# matherBoard.net
KiCad netlist of a schematic drawn in EAGLE
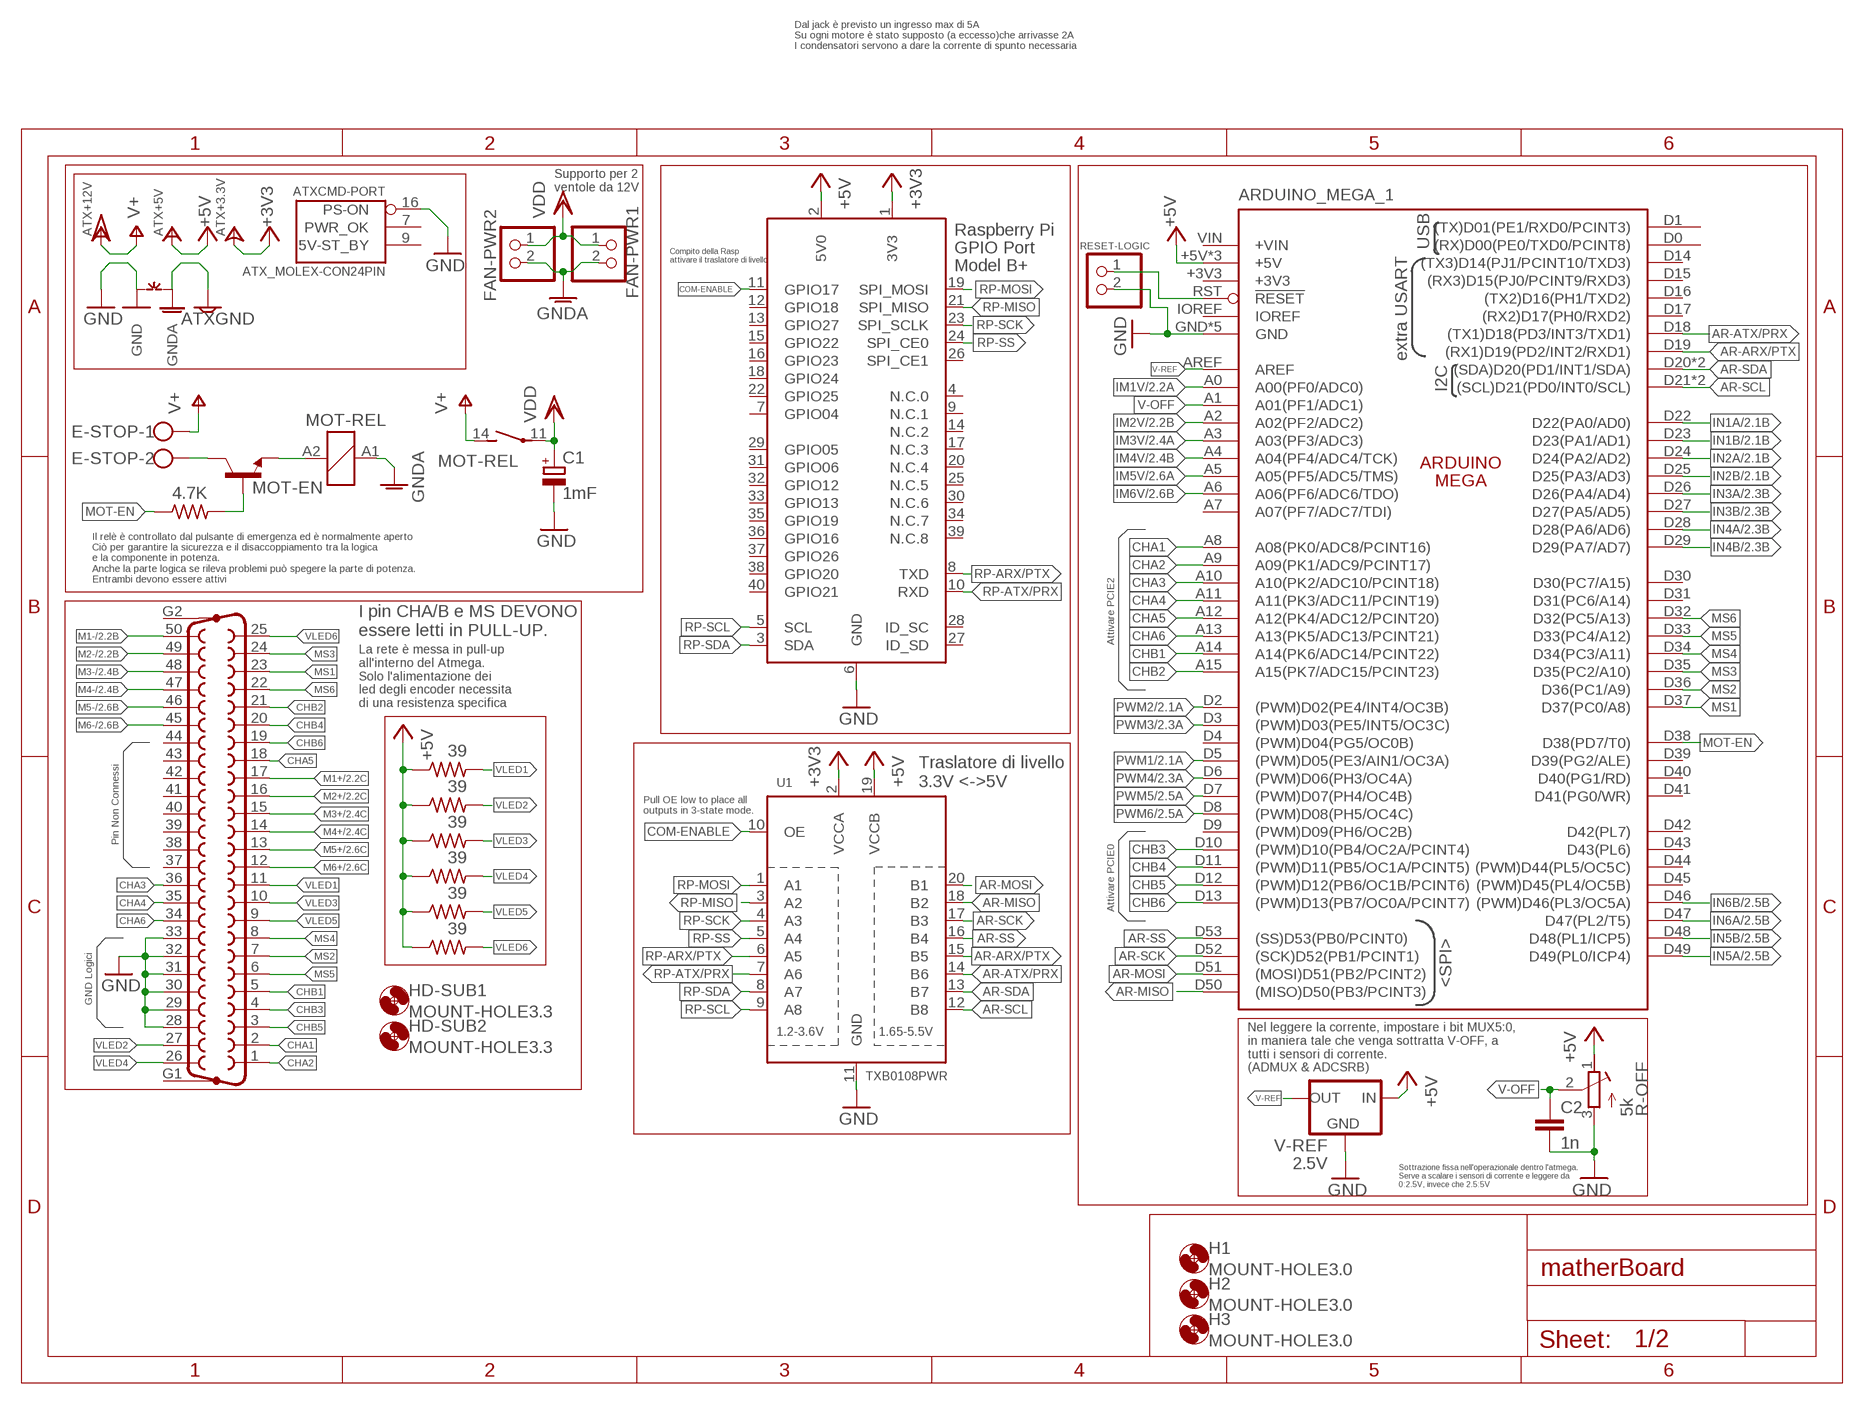
[diagram p0: schematic, sheet 1]
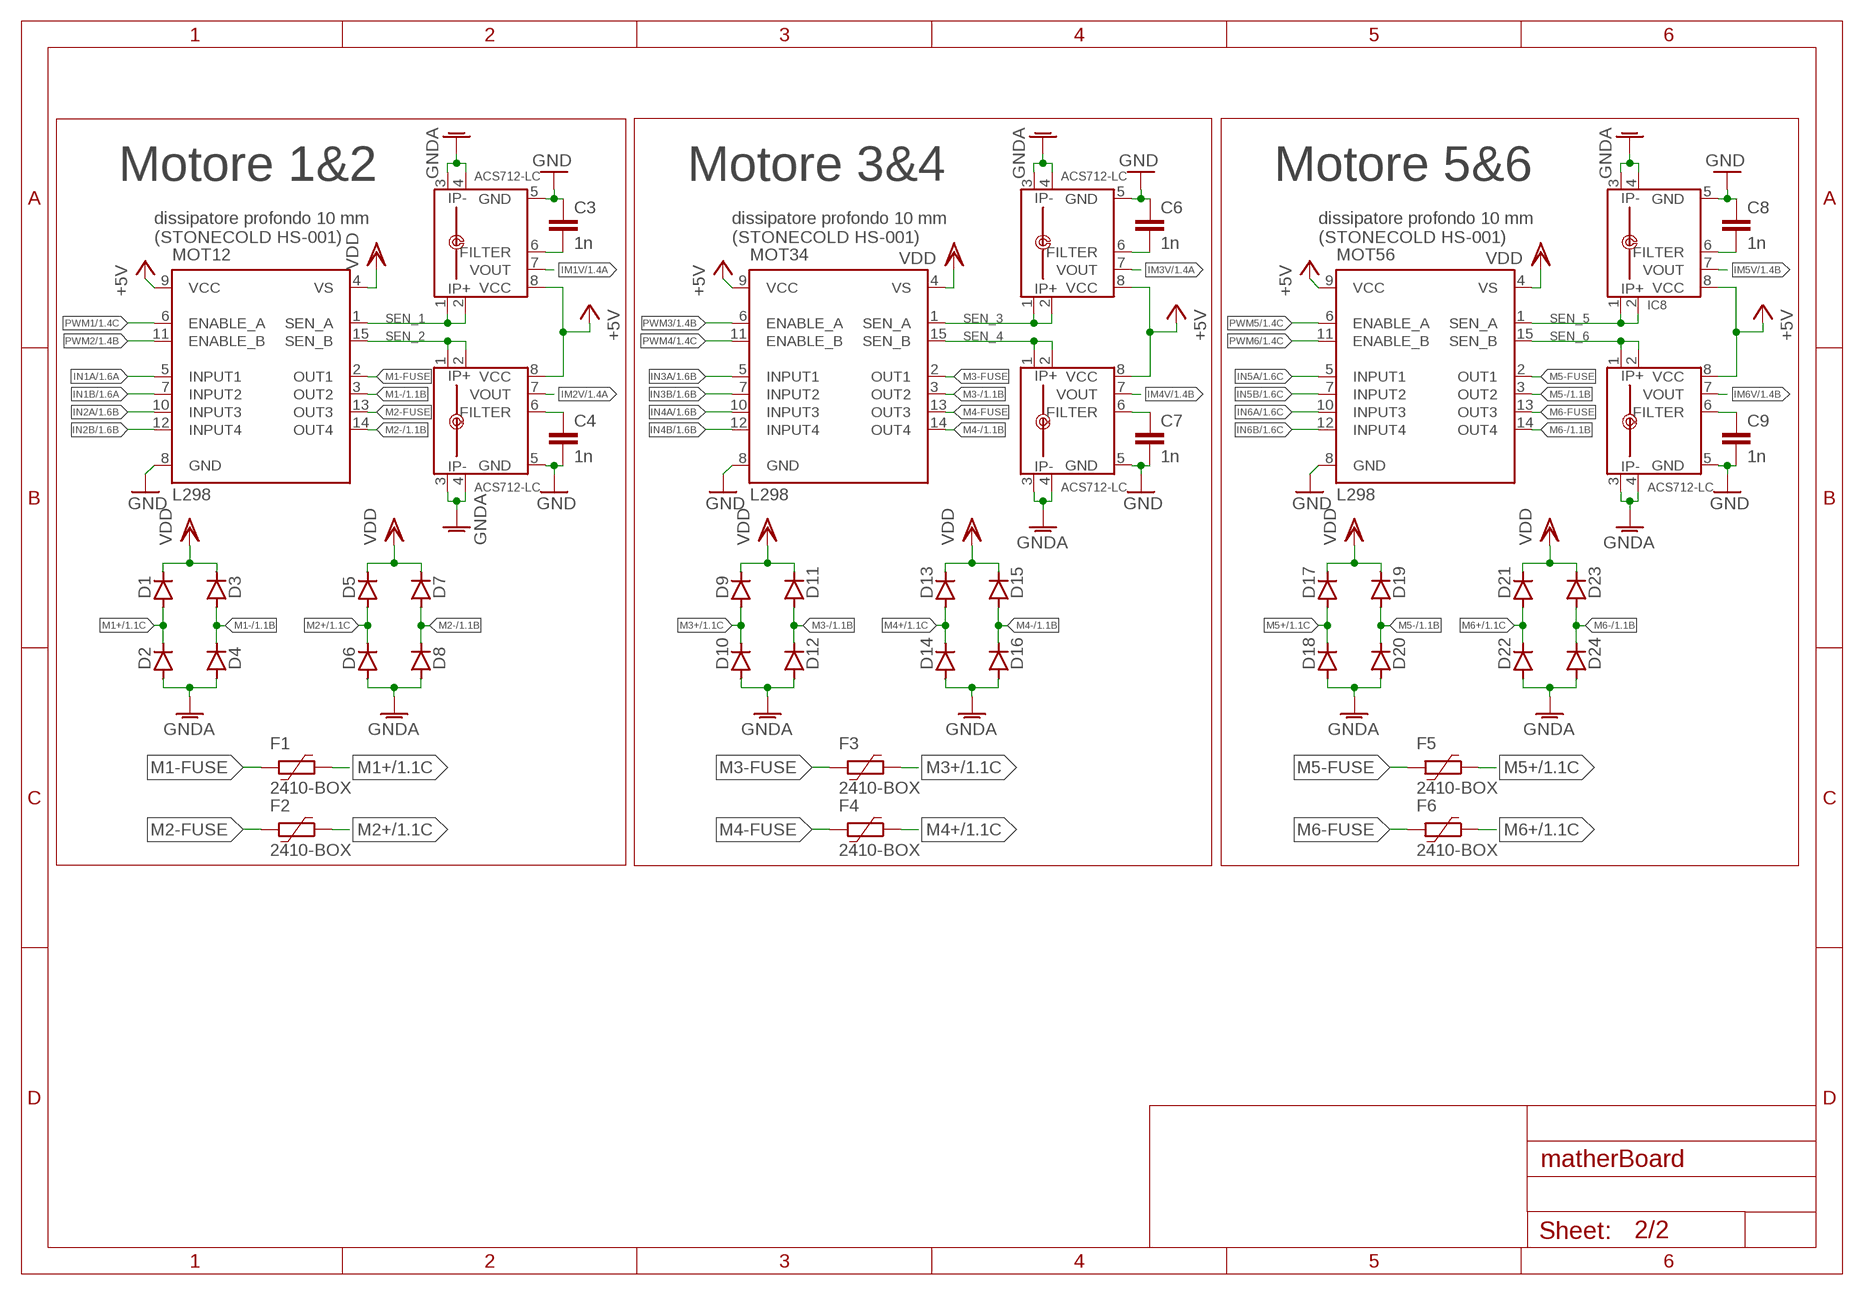
[diagram p1: schematic, sheet 2]

(export (version "E")
  (design (tool "Eeschema 10.0.6"))
  (components
    (comp (ref "C3")
      (value "1n")
      (footprint "eagle-import:C025-024X044")
      (libsource (lib "eagle-import") (part "C-EU025-024X044"))
    )
    (comp (ref "C4")
      (value "1n")
      (footprint "eagle-import:C025-024X044")
      (libsource (lib "eagle-import") (part "C-EU025-024X044"))
    )
    (comp (ref "C6")
      (value "1n")
      (footprint "eagle-import:C025-024X044")
      (libsource (lib "eagle-import") (part "C-EU025-024X044"))
    )
    (comp (ref "C7")
      (value "1n")
      (footprint "eagle-import:C025-024X044")
      (libsource (lib "eagle-import") (part "C-EU025-024X044"))
    )
    (comp (ref "C8")
      (value "1n")
      (footprint "eagle-import:C025-024X044")
      (libsource (lib "eagle-import") (part "C-EU025-024X044"))
    )
    (comp (ref "C9")
      (value "1n")
      (footprint "eagle-import:C025-024X044")
      (libsource (lib "eagle-import") (part "C-EU025-024X044"))
    )
    (comp (ref "D1")
      (value "ES2D")
      (footprint "eagle-import:SMB")
      (libsource (lib "eagle-import") (part "ES2D"))
    )
    (comp (ref "D2")
      (value "ES2D")
      (footprint "eagle-import:SMB")
      (libsource (lib "eagle-import") (part "ES2D"))
    )
    (comp (ref "D3")
      (value "ES2D")
      (footprint "eagle-import:SMB")
      (libsource (lib "eagle-import") (part "ES2D"))
    )
    (comp (ref "D4")
      (value "ES2D")
      (footprint "eagle-import:SMB")
      (libsource (lib "eagle-import") (part "ES2D"))
    )
    (comp (ref "D5")
      (value "ES2D")
      (footprint "eagle-import:SMB")
      (libsource (lib "eagle-import") (part "ES2D"))
    )
    (comp (ref "D6")
      (value "ES2D")
      (footprint "eagle-import:SMB")
      (libsource (lib "eagle-import") (part "ES2D"))
    )
    (comp (ref "D7")
      (value "ES2D")
      (footprint "eagle-import:SMB")
      (libsource (lib "eagle-import") (part "ES2D"))
    )
    (comp (ref "D8")
      (value "ES2D")
      (footprint "eagle-import:SMB")
      (libsource (lib "eagle-import") (part "ES2D"))
    )
    (comp (ref "D9")
      (value "ES2D")
      (footprint "eagle-import:SMB")
      (libsource (lib "eagle-import") (part "ES2D"))
    )
    (comp (ref "D10")
      (value "ES2D")
      (footprint "eagle-import:SMB")
      (libsource (lib "eagle-import") (part "ES2D"))
    )
    (comp (ref "D11")
      (value "ES2D")
      (footprint "eagle-import:SMB")
      (libsource (lib "eagle-import") (part "ES2D"))
    )
    (comp (ref "D12")
      (value "ES2D")
      (footprint "eagle-import:SMB")
      (libsource (lib "eagle-import") (part "ES2D"))
    )
    (comp (ref "D13")
      (value "ES2D")
      (footprint "eagle-import:SMB")
      (libsource (lib "eagle-import") (part "ES2D"))
    )
    (comp (ref "D14")
      (value "ES2D")
      (footprint "eagle-import:SMB")
      (libsource (lib "eagle-import") (part "ES2D"))
    )
    (comp (ref "D15")
      (value "ES2D")
      (footprint "eagle-import:SMB")
      (libsource (lib "eagle-import") (part "ES2D"))
    )
    (comp (ref "D16")
      (value "ES2D")
      (footprint "eagle-import:SMB")
      (libsource (lib "eagle-import") (part "ES2D"))
    )
    (comp (ref "D17")
      (value "ES2D")
      (footprint "eagle-import:SMB")
      (libsource (lib "eagle-import") (part "ES2D"))
    )
    (comp (ref "D18")
      (value "ES2D")
      (footprint "eagle-import:SMB")
      (libsource (lib "eagle-import") (part "ES2D"))
    )
    (comp (ref "D19")
      (value "ES2D")
      (footprint "eagle-import:SMB")
      (libsource (lib "eagle-import") (part "ES2D"))
    )
    (comp (ref "D20")
      (value "ES2D")
      (footprint "eagle-import:SMB")
      (libsource (lib "eagle-import") (part "ES2D"))
    )
    (comp (ref "D21")
      (value "ES2D")
      (footprint "eagle-import:SMB")
      (libsource (lib "eagle-import") (part "ES2D"))
    )
    (comp (ref "D22")
      (value "ES2D")
      (footprint "eagle-import:SMB")
      (libsource (lib "eagle-import") (part "ES2D"))
    )
    (comp (ref "D23")
      (value "ES2D")
      (footprint "eagle-import:SMB")
      (libsource (lib "eagle-import") (part "ES2D"))
    )
    (comp (ref "D24")
      (value "ES2D")
      (footprint "eagle-import:SMB")
      (libsource (lib "eagle-import") (part "ES2D"))
    )
    (comp (ref "F1")
      (value "2410-BOX")
      (footprint "eagle-import:BELFUSE0679-3000-12")
      (libsource (lib "eagle-import") (part "?2410-BOX"))
    )
    (comp (ref "F2")
      (value "2410-BOX")
      (footprint "eagle-import:BELFUSE0679-3000-12")
      (libsource (lib "eagle-import") (part "?2410-BOX"))
    )
    (comp (ref "F3")
      (value "2410-BOX")
      (footprint "eagle-import:BELFUSE0679-3000-12")
      (libsource (lib "eagle-import") (part "?2410-BOX"))
    )
    (comp (ref "F4")
      (value "2410-BOX")
      (footprint "eagle-import:BELFUSE0679-3000-12")
      (libsource (lib "eagle-import") (part "?2410-BOX"))
    )
    (comp (ref "F5")
      (value "2410-BOX")
      (footprint "eagle-import:BELFUSE0679-3000-12")
      (libsource (lib "eagle-import") (part "?2410-BOX"))
    )
    (comp (ref "F6")
      (value "2410-BOX")
      (footprint "eagle-import:BELFUSE0679-3000-12")
      (libsource (lib "eagle-import") (part "?2410-BOX"))
    )
    (comp (ref "IC2")
      (value "ACS712-LC")
      (footprint "eagle-import:SOIC8")
      (libsource (lib "eagle-import") (part "ACS712-LC"))
    )
    (comp (ref "IC3")
      (value "ACS712-LC")
      (footprint "eagle-import:SOIC8")
      (libsource (lib "eagle-import") (part "ACS712-LC"))
    )
    (comp (ref "IC5")
      (value "ACS712-LC")
      (footprint "eagle-import:SOIC8")
      (libsource (lib "eagle-import") (part "ACS712-LC"))
    )
    (comp (ref "IC6")
      (value "ACS712-LC")
      (footprint "eagle-import:SOIC8")
      (libsource (lib "eagle-import") (part "ACS712-LC"))
    )
    (comp (ref "IC8")
      (value "ACS712-LC")
      (footprint "eagle-import:SOIC8")
      (libsource (lib "eagle-import") (part "ACS712-LC"))
    )
    (comp (ref "IC9")
      (value "ACS712-LC")
      (footprint "eagle-import:SOIC8")
      (libsource (lib "eagle-import") (part "ACS712-LC"))
    )
    (comp (ref "MOT12")
      (value "L298")
      (footprint "eagle-import:MULTIWATT-15")
      (fields (field (name "MPN") "L298N"))
      (libsource (lib "eagle-import") (part "L298"))
    )
    (comp (ref "MOT34")
      (value "L298")
      (footprint "eagle-import:MULTIWATT-15")
      (fields (field (name "MPN") "L298N"))
      (libsource (lib "eagle-import") (part "L298"))
    )
    (comp (ref "MOT56")
      (value "L298")
      (footprint "eagle-import:MULTIWATT-15")
      (fields (field (name "MPN") "L298N"))
      (libsource (lib "eagle-import") (part "L298"))
    )
    (comp (ref "ARDUINO_MEGA_1")
      (value "MEGA_ARDUINONO-HOLE")
      (footprint "eagle-import:MEGA-NO-HOLE")
      (libsource (lib "eagle-import") (part "MEGA_ARDUINONO-HOLE"))
    )
    (comp (ref "ATX")
      (value "ATX_MOLEX-CON24PIN")
      (footprint "eagle-import:5566-24")
      (libsource (lib "eagle-import") (part "ATX_MOLEX-CON24PIN"))
    )
    (comp (ref "C1")
      (value "1mF")
      (footprint "eagle-import:E5-13")
      (libsource (lib "eagle-import") (part "CPOL-EUE5-13"))
    )
    (comp (ref "C2")
      (value "1n")
      (footprint "eagle-import:C025-024X044")
      (libsource (lib "eagle-import") (part "C-EU025-024X044"))
    )
    (comp (ref "D-SUB50")
      (value "F50VP")
      (footprint "eagle-import:F50VP")
      (libsource (lib "eagle-import") (part "F50VP"))
    )
    (comp (ref "E-STOP")
      (value "W237-102")
      (footprint "eagle-import:W237-102")
      (fields (field (name "MPN") "237-102"))
      (libsource (lib "eagle-import") (part "W237-102"))
    )
    (comp (ref "FAN-PWR1")
      (value "PINHD-1X2")
      (footprint "eagle-import:1X02")
      (libsource (lib "eagle-import") (part "PINHD-1X2"))
    )
    (comp (ref "FAN-PWR2")
      (value "PINHD-1X2")
      (footprint "eagle-import:1X02")
      (libsource (lib "eagle-import") (part "PINHD-1X2"))
    )
    (comp (ref "H1")
      (value "MOUNT-HOLE3.0")
      (footprint "eagle-import:3,0")
      (libsource (lib "eagle-import") (part "MOUNT-HOLE3.0"))
    )
    (comp (ref "H2")
      (value "MOUNT-HOLE3.0")
      (footprint "eagle-import:3,0")
      (libsource (lib "eagle-import") (part "MOUNT-HOLE3.0"))
    )
    (comp (ref "H3")
      (value "MOUNT-HOLE3.0")
      (footprint "eagle-import:3,0")
      (libsource (lib "eagle-import") (part "MOUNT-HOLE3.0"))
    )
    (comp (ref "HD-SUB1")
      (value "MOUNT-HOLE3.3")
      (footprint "eagle-import:3,3")
      (libsource (lib "eagle-import") (part "MOUNT-HOLE3.3"))
    )
    (comp (ref "HD-SUB2")
      (value "MOUNT-HOLE3.3")
      (footprint "eagle-import:3,3")
      (libsource (lib "eagle-import") (part "MOUNT-HOLE3.3"))
    )
    (comp (ref "MOT-EN")
      (value "2N5550-NPN-TO92-CBE")
      (footprint "eagle-import:TO92-CBE")
      (libsource (lib "eagle-import") (part "-NPN-TO92-CBE2N5550"))
    )
    (comp (ref "MOT-REL")
      (value "RP530006")
      (footprint "eagle-import:RP53")
      (libsource (lib "eagle-import") (part "RP530006"))
    )
    (comp (ref "R-OFF")
      (value "5k")
      (footprint "eagle-import:RTRIMT93YA")
      (libsource (lib "eagle-import") (part "R-TRIMMT93YA"))
    )
    (comp (ref "R1")
      (value "39")
      (footprint "eagle-import:0204_5")
      (libsource (lib "eagle-import") (part "R-US_0204/5"))
    )
    (comp (ref "R2")
      (value "39")
      (footprint "eagle-import:0204_5")
      (libsource (lib "eagle-import") (part "R-US_0204/5"))
    )
    (comp (ref "R3")
      (value "39")
      (footprint "eagle-import:0204_5")
      (libsource (lib "eagle-import") (part "R-US_0204/5"))
    )
    (comp (ref "R4")
      (value "39")
      (footprint "eagle-import:0204_5")
      (libsource (lib "eagle-import") (part "R-US_0204/5"))
    )
    (comp (ref "R5")
      (value "39")
      (footprint "eagle-import:0204_5")
      (libsource (lib "eagle-import") (part "R-US_0204/5"))
    )
    (comp (ref "R6")
      (value "39")
      (footprint "eagle-import:0204_5")
      (libsource (lib "eagle-import") (part "R-US_0204/5"))
    )
    (comp (ref "R7")
      (value "4.7K")
      (footprint "eagle-import:0204_7")
      (libsource (lib "eagle-import") (part "R-US_0204/7"))
    )
    (comp (ref "RASPBERRY-PY")
      (value "RASPI_GPIO_B+_BOX")
      (footprint "eagle-import:RASPI_GPIO_B+_BOX")
      (libsource (lib "eagle-import") (part "RASPI_GPIO_B+_BOX"))
    )
    (comp (ref "RESET-LOGIC")
      (value "PINHD-1X2")
      (footprint "eagle-import:1X02")
      (libsource (lib "eagle-import") (part "PINHD-1X2"))
    )
    (comp (ref "U1")
      (value "TXB0108PWR")
      (footprint "eagle-import:TSSOP20")
      (fields (field (name "MF") "Texas Instruments"))
      (libsource (lib "eagle-import") (part "TXB0108PWR"))
    )
    (comp (ref "V-REF")
      (value "2.5V")
      (footprint "eagle-import:SOT23")
      (libsource (lib "eagle-import") (part "XC63FPM"))
    )
    (comp (ref "~NUDEV~1")
      (value "GND-GNDA1,27MM")
      (footprint "eagle-import:GND-GNDA-1,27MM")
      (libsource (lib "eagle-import") (part "GND-GNDA1,27MM"))
    )
  )
  (nets
    (net (code "1") (name "+3V3") (class "Default")
      (node (ref "ATX") (pin "1") (pinfunction "+3V3-ATX_1") (pintype "power_in"))
      (node (ref "ATX") (pin "12") (pinfunction "+3V3-ATX_12") (pintype "power_in"))
      (node (ref "ATX") (pin "13") (pinfunction "+3V3-ATX_13") (pintype "power_in"))
      (node (ref "ATX") (pin "2") (pinfunction "+3V3-ATX_2") (pintype "power_in"))
      (node (ref "RASPBERRY-PY") (pin "1") (pinfunction "3V3_1") (pintype "power_in"))
      (node (ref "U1") (pin "2") (pinfunction "VCCA_2") (pintype "bidirectional"))
    )
    (net (code "2") (name "+5V") (class "Default")
      (node (ref "ARDUINO_MEGA_1") (pin "+5V") (pinfunction "+5V_+5V") (pintype "bidirectional"))
      (node (ref "ARDUINO_MEGA_1") (pin "+5V1") (pinfunction "+5V_+5V1") (pintype "bidirectional"))
      (node (ref "ARDUINO_MEGA_1") (pin "+5V2") (pinfunction "+5V_+5V2") (pintype "bidirectional"))
      (node (ref "ATX") (pin "21") (pinfunction "+5V-ATX_21") (pintype "power_in"))
      (node (ref "ATX") (pin "22") (pinfunction "+5V-ATX_22") (pintype "power_in"))
      (node (ref "ATX") (pin "23") (pinfunction "+5V-ATX_23") (pintype "power_in"))
      (node (ref "ATX") (pin "4") (pinfunction "+5V-ATX_4") (pintype "power_in"))
      (node (ref "ATX") (pin "6") (pinfunction "+5V-ATX_6") (pintype "power_in"))
      (node (ref "IC2") (pin "8") (pinfunction "VCC_8") (pintype "power_in"))
      (node (ref "IC3") (pin "8") (pinfunction "VCC_8") (pintype "power_in"))
      (node (ref "IC5") (pin "8") (pinfunction "VCC_8") (pintype "power_in"))
      (node (ref "IC6") (pin "8") (pinfunction "VCC_8") (pintype "power_in"))
      (node (ref "IC8") (pin "8") (pinfunction "VCC_8") (pintype "power_in"))
      (node (ref "IC9") (pin "8") (pinfunction "VCC_8") (pintype "power_in"))
      (node (ref "MOT12") (pin "9") (pinfunction "VCC_9") (pintype "power_in"))
      (node (ref "MOT34") (pin "9") (pinfunction "VCC_9") (pintype "power_in"))
      (node (ref "MOT56") (pin "9") (pinfunction "VCC_9") (pintype "power_in"))
      (node (ref "R-OFF") (pin "1") (pinfunction "E_1") (pintype "passive"))
      (node (ref "R1") (pin "1") (pinfunction "1_1") (pintype "passive"))
      (node (ref "R2") (pin "1") (pinfunction "1_1") (pintype "passive"))
      (node (ref "R3") (pin "1") (pinfunction "1_1") (pintype "passive"))
      (node (ref "R4") (pin "1") (pinfunction "1_1") (pintype "passive"))
      (node (ref "R5") (pin "1") (pinfunction "1_1") (pintype "passive"))
      (node (ref "R6") (pin "1") (pinfunction "1_1") (pintype "passive"))
      (node (ref "RASPBERRY-PY") (pin "2") (pinfunction "5V0_2") (pintype "power_in"))
      (node (ref "U1") (pin "19") (pinfunction "VCCB_19") (pintype "bidirectional"))
      (node (ref "V-REF") (pin "3") (pinfunction "IN_3") (pintype "input"))
    )
    (net (code "3") (name "AR-ARX{slash}PTX") (class "Default")
      (node (ref "ARDUINO_MEGA_1") (pin "D19") (pinfunction "(RX1)D19(PD2/INT2/RXD1)_D19") (pintype "bidirectional"))
      (node (ref "U1") (pin "15") (pinfunction "B5_15") (pintype "bidirectional"))
    )
    (net (code "4") (name "AR-ATX{slash}PRX") (class "Default")
      (node (ref "ARDUINO_MEGA_1") (pin "D18") (pinfunction "(TX1)D18(PD3/INT3/TXD1)_D18") (pintype "bidirectional"))
      (node (ref "U1") (pin "14") (pinfunction "B6_14") (pintype "bidirectional"))
    )
    (net (code "5") (name "AR-MISO") (class "Default")
      (node (ref "ARDUINO_MEGA_1") (pin "D50") (pinfunction "(MISO)D50(PB3/PCINT3)_D50") (pintype "bidirectional"))
      (node (ref "U1") (pin "18") (pinfunction "B2_18") (pintype "bidirectional"))
    )
    (net (code "6") (name "AR-MOSI") (class "Default")
      (node (ref "ARDUINO_MEGA_1") (pin "D51") (pinfunction "(MOSI)D51(PB2/PCINT2)_D51") (pintype "bidirectional"))
      (node (ref "U1") (pin "20") (pinfunction "B1_20") (pintype "bidirectional"))
    )
    (net (code "7") (name "AR-SCK") (class "Default")
      (node (ref "ARDUINO_MEGA_1") (pin "D52") (pinfunction "(SCK)D52(PB1/PCINT1)_D52") (pintype "bidirectional"))
      (node (ref "U1") (pin "17") (pinfunction "B3_17") (pintype "bidirectional"))
    )
    (net (code "8") (name "AR-SCL") (class "Default")
      (node (ref "ARDUINO_MEGA_1") (pin "D21") (pinfunction "(SCL)D21(PD0/INT0/SCL)_D21") (pintype "bidirectional"))
      (node (ref "ARDUINO_MEGA_1") (pin "SCL1") (pinfunction "(SCL)D21(PD0/INT0/SCL)_SCL1") (pintype "bidirectional"))
      (node (ref "U1") (pin "12") (pinfunction "B8_12") (pintype "bidirectional"))
    )
    (net (code "9") (name "AR-SDA") (class "Default")
      (node (ref "ARDUINO_MEGA_1") (pin "D20") (pinfunction "(SDA)D20(PD1/INT1/SDA)_D20") (pintype "bidirectional"))
      (node (ref "ARDUINO_MEGA_1") (pin "SDA1") (pinfunction "(SDA)D20(PD1/INT1/SDA)_SDA1") (pintype "bidirectional"))
      (node (ref "U1") (pin "13") (pinfunction "B7_13") (pintype "bidirectional"))
    )
    (net (code "10") (name "AR-SS") (class "Default")
      (node (ref "ARDUINO_MEGA_1") (pin "D53") (pinfunction "(SS)D53(PB0/PCINT0)_D53") (pintype "bidirectional"))
      (node (ref "U1") (pin "16") (pinfunction "B4_16") (pintype "bidirectional"))
    )
    (net (code "11") (name "CHA1") (class "Default")
      (node (ref "ARDUINO_MEGA_1") (pin "A8") (pinfunction "A08(PK0/ADC8/PCINT16)_A8") (pintype "bidirectional"))
      (node (ref "D-SUB50") (pin "2") (pinfunction "2_2") (pintype "passive"))
    )
    (net (code "12") (name "CHA2") (class "Default")
      (node (ref "ARDUINO_MEGA_1") (pin "A9") (pinfunction "A09(PK1/ADC9/PCINT17)_A9") (pintype "bidirectional"))
      (node (ref "D-SUB50") (pin "1") (pinfunction "1_1") (pintype "passive"))
    )
    (net (code "13") (name "CHA3") (class "Default")
      (node (ref "ARDUINO_MEGA_1") (pin "A10") (pinfunction "A10(PK2/ADC10/PCINT18)_A10") (pintype "bidirectional"))
      (node (ref "D-SUB50") (pin "36") (pinfunction "36_36") (pintype "passive"))
    )
    (net (code "14") (name "CHA4") (class "Default")
      (node (ref "ARDUINO_MEGA_1") (pin "A11") (pinfunction "A11(PK3/ADC11/PCINT19)_A11") (pintype "bidirectional"))
      (node (ref "D-SUB50") (pin "35") (pinfunction "35_35") (pintype "passive"))
    )
    (net (code "15") (name "CHA5") (class "Default")
      (node (ref "ARDUINO_MEGA_1") (pin "A12") (pinfunction "A12(PK4/ADC12/PCINT20)_A12") (pintype "bidirectional"))
      (node (ref "D-SUB50") (pin "18") (pinfunction "18_18") (pintype "passive"))
    )
    (net (code "16") (name "CHA6") (class "Default")
      (node (ref "ARDUINO_MEGA_1") (pin "A13") (pinfunction "A13(PK5/ADC13/PCINT21)_A13") (pintype "bidirectional"))
      (node (ref "D-SUB50") (pin "34") (pinfunction "34_34") (pintype "passive"))
    )
    (net (code "17") (name "CHB1") (class "Default")
      (node (ref "ARDUINO_MEGA_1") (pin "A14") (pinfunction "A14(PK6/ADC14/PCINT22)_A14") (pintype "bidirectional"))
      (node (ref "D-SUB50") (pin "5") (pinfunction "5_5") (pintype "passive"))
    )
    (net (code "18") (name "CHB2") (class "Default")
      (node (ref "ARDUINO_MEGA_1") (pin "A15") (pinfunction "A15(PK7/ADC15/PCINT23)_A15") (pintype "bidirectional"))
      (node (ref "D-SUB50") (pin "21") (pinfunction "21_21") (pintype "passive"))
    )
    (net (code "19") (name "CHB3") (class "Default")
      (node (ref "ARDUINO_MEGA_1") (pin "D10") (pinfunction "(PWM)D10(PB4/OC2A/PCINT4)_D10") (pintype "bidirectional"))
      (node (ref "D-SUB50") (pin "4") (pinfunction "4_4") (pintype "passive"))
    )
    (net (code "20") (name "CHB4") (class "Default")
      (node (ref "ARDUINO_MEGA_1") (pin "D11") (pinfunction "(PWM)D11(PB5/OC1A/PCINT5)_D11") (pintype "bidirectional"))
      (node (ref "D-SUB50") (pin "20") (pinfunction "20_20") (pintype "passive"))
    )
    (net (code "21") (name "CHB5") (class "Default")
      (node (ref "ARDUINO_MEGA_1") (pin "D12") (pinfunction "(PWM)D12(PB6/OC1B/PCINT6)_D12") (pintype "bidirectional"))
      (node (ref "D-SUB50") (pin "3") (pinfunction "3_3") (pintype "passive"))
    )
    (net (code "22") (name "CHB6") (class "Default")
      (node (ref "ARDUINO_MEGA_1") (pin "D13") (pinfunction "(PWM)D13(PB7/OC0A/PCINT7)_D13") (pintype "bidirectional"))
      (node (ref "D-SUB50") (pin "19") (pinfunction "19_19") (pintype "passive"))
    )
    (net (code "23") (name "COM-ENABLE") (class "Default")
      (node (ref "RASPBERRY-PY") (pin "11") (pinfunction "GPIO17_11") (pintype "bidirectional"))
      (node (ref "U1") (pin "10") (pinfunction "OE_10") (pintype "bidirectional"))
    )
    (net (code "24") (name "GND") (class "Default")
      (node (ref "ARDUINO_MEGA_1") (pin "GND") (pinfunction "GND_GND") (pintype "bidirectional"))
      (node (ref "ARDUINO_MEGA_1") (pin "GND1") (pinfunction "GND_GND1") (pintype "bidirectional"))
      (node (ref "ARDUINO_MEGA_1") (pin "GND2") (pinfunction "GND_GND2") (pintype "bidirectional"))
      (node (ref "ARDUINO_MEGA_1") (pin "GND3") (pinfunction "GND_GND3") (pintype "bidirectional"))
      (node (ref "ARDUINO_MEGA_1") (pin "GND4") (pinfunction "GND_GND4") (pintype "bidirectional"))
      (node (ref "ATX") (pin "16") (pinfunction "PS-ON_16") (pintype "input"))
      (node (ref "C1") (pin "-") (pinfunction "-_-") (pintype "passive"))
      (node (ref "C2") (pin "2") (pinfunction "2_2") (pintype "passive"))
      (node (ref "C3") (pin "1") (pinfunction "1_1") (pintype "passive"))
      (node (ref "C4") (pin "2") (pinfunction "2_2") (pintype "passive"))
      (node (ref "C6") (pin "1") (pinfunction "1_1") (pintype "passive"))
      (node (ref "C7") (pin "2") (pinfunction "2_2") (pintype "passive"))
      (node (ref "C8") (pin "1") (pinfunction "1_1") (pintype "passive"))
      (node (ref "C9") (pin "2") (pinfunction "2_2") (pintype "passive"))
      (node (ref "D-SUB50") (pin "28") (pinfunction "28_28") (pintype "passive"))
      (node (ref "D-SUB50") (pin "29") (pinfunction "29_29") (pintype "passive"))
      (node (ref "D-SUB50") (pin "30") (pinfunction "30_30") (pintype "passive"))
      (node (ref "D-SUB50") (pin "31") (pinfunction "31_31") (pintype "passive"))
      (node (ref "D-SUB50") (pin "32") (pinfunction "32_32") (pintype "passive"))
      (node (ref "D-SUB50") (pin "33") (pinfunction "33_33") (pintype "passive"))
      (node (ref "IC2") (pin "5") (pinfunction "GND_5") (pintype "power_in"))
      (node (ref "IC3") (pin "5") (pinfunction "GND_5") (pintype "power_in"))
      (node (ref "IC5") (pin "5") (pinfunction "GND_5") (pintype "power_in"))
      (node (ref "IC6") (pin "5") (pinfunction "GND_5") (pintype "power_in"))
      (node (ref "IC8") (pin "5") (pinfunction "GND_5") (pintype "power_in"))
      (node (ref "IC9") (pin "5") (pinfunction "GND_5") (pintype "power_in"))
      (node (ref "MOT12") (pin "8") (pinfunction "GND_8") (pintype "power_in"))
      (node (ref "MOT34") (pin "8") (pinfunction "GND_8") (pintype "power_in"))
      (node (ref "MOT56") (pin "8") (pinfunction "GND_8") (pintype "power_in"))
      (node (ref "R-OFF") (pin "3") (pinfunction "A_3") (pintype "passive"))
      (node (ref "RASPBERRY-PY") (pin "6") (pinfunction "GND_6") (pintype "power_in"))
      (node (ref "RESET-LOGIC") (pin "2") (pinfunction "2_2") (pintype "passive"))
      (node (ref "U1") (pin "11") (pinfunction "GND_11") (pintype "bidirectional"))
      (node (ref "V-REF") (pin "1") (pinfunction "GND_1") (pintype "input"))
      (node (ref "~NUDEV~1") (pin "GND") (pinfunction "GND_GND") (pintype "power_in"))
    )
    (net (code "25") (name "GNDA") (class "Default")
      (node (ref "ATX") (pin "15") (pinfunction "GND-ATX_15") (pintype "power_in"))
      (node (ref "ATX") (pin "17") (pinfunction "GND-ATX_17") (pintype "power_in"))
      (node (ref "ATX") (pin "18") (pinfunction "GND-ATX_18") (pintype "power_in"))
      (node (ref "ATX") (pin "19") (pinfunction "GND-ATX_19") (pintype "power_in"))
      (node (ref "ATX") (pin "24") (pinfunction "GND-ATX_24") (pintype "power_in"))
      (node (ref "ATX") (pin "3") (pinfunction "GND-ATX_3") (pintype "power_in"))
      (node (ref "ATX") (pin "5") (pinfunction "GND-ATX_5") (pintype "power_in"))
      (node (ref "ATX") (pin "8") (pinfunction "GND-ATX_8") (pintype "power_in"))
      (node (ref "D10") (pin "A") (pinfunction "A_A") (pintype "passive"))
      (node (ref "D12") (pin "A") (pinfunction "A_A") (pintype "passive"))
      (node (ref "D14") (pin "A") (pinfunction "A_A") (pintype "passive"))
      (node (ref "D16") (pin "A") (pinfunction "A_A") (pintype "passive"))
      (node (ref "D18") (pin "A") (pinfunction "A_A") (pintype "passive"))
      (node (ref "D2") (pin "A") (pinfunction "A_A") (pintype "passive"))
      (node (ref "D20") (pin "A") (pinfunction "A_A") (pintype "passive"))
      (node (ref "D22") (pin "A") (pinfunction "A_A") (pintype "passive"))
      (node (ref "D24") (pin "A") (pinfunction "A_A") (pintype "passive"))
      (node (ref "D4") (pin "A") (pinfunction "A_A") (pintype "passive"))
      (node (ref "D6") (pin "A") (pinfunction "A_A") (pintype "passive"))
      (node (ref "D8") (pin "A") (pinfunction "A_A") (pintype "passive"))
      (node (ref "FAN-PWR1") (pin "2") (pinfunction "2_2") (pintype "passive"))
      (node (ref "FAN-PWR2") (pin "2") (pinfunction "2_2") (pintype "passive"))
      (node (ref "IC2") (pin "3") (pinfunction "IP-_3") (pintype "passive"))
      (node (ref "IC2") (pin "4") (pinfunction "IP-1_4") (pintype "passive"))
      (node (ref "IC3") (pin "3") (pinfunction "IP-_3") (pintype "passive"))
      (node (ref "IC3") (pin "4") (pinfunction "IP-1_4") (pintype "passive"))
      (node (ref "IC5") (pin "3") (pinfunction "IP-_3") (pintype "passive"))
      (node (ref "IC5") (pin "4") (pinfunction "IP-1_4") (pintype "passive"))
      (node (ref "IC6") (pin "3") (pinfunction "IP-_3") (pintype "passive"))
      (node (ref "IC6") (pin "4") (pinfunction "IP-1_4") (pintype "passive"))
      (node (ref "IC8") (pin "3") (pinfunction "IP-_3") (pintype "passive"))
      (node (ref "IC8") (pin "4") (pinfunction "IP-1_4") (pintype "passive"))
      (node (ref "IC9") (pin "3") (pinfunction "IP-_3") (pintype "passive"))
      (node (ref "IC9") (pin "4") (pinfunction "IP-1_4") (pintype "passive"))
      (node (ref "MOT-REL") (pin "A1") (pinfunction "1_A1") (pintype "passive"))
      (node (ref "~NUDEV~1") (pin "GNDA") (pinfunction "GNDA_GNDA") (pintype "power_in"))
    )
    (net (code "26") (name "IM1V") (class "Default")
      (node (ref "ARDUINO_MEGA_1") (pin "A0") (pinfunction "A00(PF0/ADC0)_A0") (pintype "bidirectional"))
      (node (ref "IC2") (pin "7") (pinfunction "VOUT_7") (pintype "output"))
    )
    (net (code "27") (name "IM2V") (class "Default")
      (node (ref "ARDUINO_MEGA_1") (pin "A2") (pinfunction "A02(PF2/ADC2)_A2") (pintype "bidirectional"))
      (node (ref "IC3") (pin "7") (pinfunction "VOUT_7") (pintype "output"))
    )
    (net (code "28") (name "IM3V") (class "Default")
      (node (ref "ARDUINO_MEGA_1") (pin "A3") (pinfunction "A03(PF3/ADC3)_A3") (pintype "bidirectional"))
      (node (ref "IC5") (pin "7") (pinfunction "VOUT_7") (pintype "output"))
    )
    (net (code "29") (name "IM4V") (class "Default")
      (node (ref "ARDUINO_MEGA_1") (pin "A4") (pinfunction "A04(PF4/ADC4/TCK)_A4") (pintype "bidirectional"))
      (node (ref "IC6") (pin "7") (pinfunction "VOUT_7") (pintype "output"))
    )
    (net (code "30") (name "IM5V") (class "Default")
      (node (ref "ARDUINO_MEGA_1") (pin "A5") (pinfunction "A05(PF5/ADC5/TMS)_A5") (pintype "bidirectional"))
      (node (ref "IC8") (pin "7") (pinfunction "VOUT_7") (pintype "output"))
    )
    (net (code "31") (name "IM6V") (class "Default")
      (node (ref "ARDUINO_MEGA_1") (pin "A6") (pinfunction "A06(PF6/ADC6/TDO)_A6") (pintype "bidirectional"))
      (node (ref "IC9") (pin "7") (pinfunction "VOUT_7") (pintype "output"))
    )
    (net (code "32") (name "IN1A") (class "Default")
      (node (ref "ARDUINO_MEGA_1") (pin "D22") (pinfunction "D22(PA0/AD0)_D22") (pintype "bidirectional"))
      (node (ref "MOT12") (pin "5") (pinfunction "INPUT1_5") (pintype "input"))
    )
    (net (code "33") (name "IN1B") (class "Default")
      (node (ref "ARDUINO_MEGA_1") (pin "D23") (pinfunction "D23(PA1/AD1)_D23") (pintype "bidirectional"))
      (node (ref "MOT12") (pin "7") (pinfunction "INPUT2_7") (pintype "input"))
    )
    (net (code "34") (name "IN2A") (class "Default")
      (node (ref "ARDUINO_MEGA_1") (pin "D24") (pinfunction "D24(PA2/AD2)_D24") (pintype "bidirectional"))
      (node (ref "MOT12") (pin "10") (pinfunction "INPUT3_10") (pintype "input"))
    )
    (net (code "35") (name "IN2B") (class "Default")
      (node (ref "ARDUINO_MEGA_1") (pin "D25") (pinfunction "D25(PA3/AD3)_D25") (pintype "bidirectional"))
      (node (ref "MOT12") (pin "12") (pinfunction "INPUT4_12") (pintype "input"))
    )
    (net (code "36") (name "IN3A") (class "Default")
      (node (ref "ARDUINO_MEGA_1") (pin "D26") (pinfunction "D26(PA4/AD4)_D26") (pintype "bidirectional"))
      (node (ref "MOT34") (pin "5") (pinfunction "INPUT1_5") (pintype "input"))
    )
    (net (code "37") (name "IN3B") (class "Default")
      (node (ref "ARDUINO_MEGA_1") (pin "D27") (pinfunction "D27(PA5/AD5)_D27") (pintype "bidirectional"))
      (node (ref "MOT34") (pin "7") (pinfunction "INPUT2_7") (pintype "input"))
    )
    (net (code "38") (name "IN4A") (class "Default")
      (node (ref "ARDUINO_MEGA_1") (pin "D28") (pinfunction "D28(PA6/AD6)_D28") (pintype "bidirectional"))
      (node (ref "MOT34") (pin "10") (pinfunction "INPUT3_10") (pintype "input"))
    )
    (net (code "39") (name "IN4B") (class "Default")
      (node (ref "ARDUINO_MEGA_1") (pin "D29") (pinfunction "D29(PA7/AD7)_D29") (pintype "bidirectional"))
      (node (ref "MOT34") (pin "12") (pinfunction "INPUT4_12") (pintype "input"))
    )
    (net (code "40") (name "IN5A") (class "Default")
      (node (ref "ARDUINO_MEGA_1") (pin "D49") (pinfunction "D49(PL0/ICP4)_D49") (pintype "bidirectional"))
      (node (ref "MOT56") (pin "5") (pinfunction "INPUT1_5") (pintype "input"))
    )
    (net (code "41") (name "IN5B") (class "Default")
      (node (ref "ARDUINO_MEGA_1") (pin "D48") (pinfunction "D48(PL1/ICP5)_D48") (pintype "bidirectional"))
      (node (ref "MOT56") (pin "7") (pinfunction "INPUT2_7") (pintype "input"))
    )
    (net (code "42") (name "IN6A") (class "Default")
      (node (ref "ARDUINO_MEGA_1") (pin "D47") (pinfunction "D47(PL2/T5)_D47") (pintype "bidirectional"))
      (node (ref "MOT56") (pin "10") (pinfunction "INPUT3_10") (pintype "input"))
    )
    (net (code "43") (name "IN6B") (class "Default")
      (node (ref "ARDUINO_MEGA_1") (pin "D46") (pinfunction "(PWM)D46(PL3/OC5A)_D46") (pintype "bidirectional"))
      (node (ref "MOT56") (pin "12") (pinfunction "INPUT4_12") (pintype "input"))
    )
    (net (code "44") (name "M1+") (class "Default")
      (node (ref "D-SUB50") (pin "17") (pinfunction "17_17") (pintype "passive"))
      (node (ref "D1") (pin "A") (pinfunction "A_A") (pintype "passive"))
      (node (ref "D2") (pin "C") (pinfunction "C_C") (pintype "passive"))
      (node (ref "F1") (pin "1") (pinfunction "1_1") (pintype "passive"))
    )
    (net (code "45") (name "M1-") (class "Default")
      (node (ref "D-SUB50") (pin "50") (pinfunction "50_50") (pintype "passive"))
      (node (ref "D3") (pin "A") (pinfunction "A_A") (pintype "passive"))
      (node (ref "D4") (pin "C") (pinfunction "C_C") (pintype "passive"))
      (node (ref "MOT12") (pin "3") (pinfunction "OUT2_3") (pintype "output"))
    )
    (net (code "46") (name "M1-FUSE") (class "Default")
      (node (ref "F1") (pin "2") (pinfunction "2_2") (pintype "passive"))
      (node (ref "MOT12") (pin "2") (pinfunction "OUT1_2") (pintype "output"))
    )
    (net (code "47") (name "M2+") (class "Default")
      (node (ref "D-SUB50") (pin "16") (pinfunction "16_16") (pintype "passive"))
      (node (ref "D5") (pin "A") (pinfunction "A_A") (pintype "passive"))
      (node (ref "D6") (pin "C") (pinfunction "C_C") (pintype "passive"))
      (node (ref "F2") (pin "1") (pinfunction "1_1") (pintype "passive"))
    )
    (net (code "48") (name "M2-") (class "Default")
      (node (ref "D-SUB50") (pin "49") (pinfunction "49_49") (pintype "passive"))
      (node (ref "D7") (pin "A") (pinfunction "A_A") (pintype "passive"))
      (node (ref "D8") (pin "C") (pinfunction "C_C") (pintype "passive"))
      (node (ref "MOT12") (pin "14") (pinfunction "OUT4_14") (pintype "output"))
    )
    (net (code "49") (name "M2-FUSE") (class "Default")
      (node (ref "F2") (pin "2") (pinfunction "2_2") (pintype "passive"))
      (node (ref "MOT12") (pin "13") (pinfunction "OUT3_13") (pintype "output"))
    )
    (net (code "50") (name "M3+") (class "Default")
      (node (ref "D-SUB50") (pin "15") (pinfunction "15_15") (pintype "passive"))
      (node (ref "D10") (pin "C") (pinfunction "C_C") (pintype "passive"))
      (node (ref "D9") (pin "A") (pinfunction "A_A") (pintype "passive"))
      (node (ref "F3") (pin "1") (pinfunction "1_1") (pintype "passive"))
    )
    (net (code "51") (name "M3-") (class "Default")
      (node (ref "D-SUB50") (pin "48") (pinfunction "48_48") (pintype "passive"))
      (node (ref "D11") (pin "A") (pinfunction "A_A") (pintype "passive"))
      (node (ref "D12") (pin "C") (pinfunction "C_C") (pintype "passive"))
      (node (ref "MOT34") (pin "3") (pinfunction "OUT2_3") (pintype "output"))
    )
    (net (code "52") (name "M3-FUSE") (class "Default")
      (node (ref "F3") (pin "2") (pinfunction "2_2") (pintype "passive"))
      (node (ref "MOT34") (pin "2") (pinfunction "OUT1_2") (pintype "output"))
    )
    (net (code "53") (name "M4+") (class "Default")
      (node (ref "D-SUB50") (pin "14") (pinfunction "14_14") (pintype "passive"))
      (node (ref "D13") (pin "A") (pinfunction "A_A") (pintype "passive"))
      (node (ref "D14") (pin "C") (pinfunction "C_C") (pintype "passive"))
      (node (ref "F4") (pin "1") (pinfunction "1_1") (pintype "passive"))
    )
    (net (code "54") (name "M4-") (class "Default")
      (node (ref "D-SUB50") (pin "47") (pinfunction "47_47") (pintype "passive"))
      (node (ref "D15") (pin "A") (pinfunction "A_A") (pintype "passive"))
      (node (ref "D16") (pin "C") (pinfunction "C_C") (pintype "passive"))
      (node (ref "MOT34") (pin "14") (pinfunction "OUT4_14") (pintype "output"))
    )
    (net (code "55") (name "M4-FUSE") (class "Default")
      (node (ref "F4") (pin "2") (pinfunction "2_2") (pintype "passive"))
      (node (ref "MOT34") (pin "13") (pinfunction "OUT3_13") (pintype "output"))
    )
    (net (code "56") (name "M5+") (class "Default")
      (node (ref "D-SUB50") (pin "13") (pinfunction "13_13") (pintype "passive"))
      (node (ref "D17") (pin "A") (pinfunction "A_A") (pintype "passive"))
      (node (ref "D18") (pin "C") (pinfunction "C_C") (pintype "passive"))
      (node (ref "F5") (pin "1") (pinfunction "1_1") (pintype "passive"))
    )
    (net (code "57") (name "M5-") (class "Default")
      (node (ref "D-SUB50") (pin "46") (pinfunction "46_46") (pintype "passive"))
      (node (ref "D19") (pin "A") (pinfunction "A_A") (pintype "passive"))
      (node (ref "D20") (pin "C") (pinfunction "C_C") (pintype "passive"))
      (node (ref "MOT56") (pin "3") (pinfunction "OUT2_3") (pintype "output"))
    )
    (net (code "58") (name "M5-FUSE") (class "Default")
      (node (ref "F5") (pin "2") (pinfunction "2_2") (pintype "passive"))
      (node (ref "MOT56") (pin "2") (pinfunction "OUT1_2") (pintype "output"))
    )
    (net (code "59") (name "M6+") (class "Default")
      (node (ref "D-SUB50") (pin "12") (pinfunction "12_12") (pintype "passive"))
      (node (ref "D21") (pin "A") (pinfunction "A_A") (pintype "passive"))
      (node (ref "D22") (pin "C") (pinfunction "C_C") (pintype "passive"))
      (node (ref "F6") (pin "1") (pinfunction "1_1") (pintype "passive"))
    )
    (net (code "60") (name "M6-") (class "Default")
      (node (ref "D-SUB50") (pin "45") (pinfunction "45_45") (pintype "passive"))
      (node (ref "D23") (pin "A") (pinfunction "A_A") (pintype "passive"))
      (node (ref "D24") (pin "C") (pinfunction "C_C") (pintype "passive"))
      (node (ref "MOT56") (pin "14") (pinfunction "OUT4_14") (pintype "output"))
    )
    (net (code "61") (name "M6-FUSE") (class "Default")
      (node (ref "F6") (pin "2") (pinfunction "2_2") (pintype "passive"))
      (node (ref "MOT56") (pin "13") (pinfunction "OUT3_13") (pintype "output"))
    )
    (net (code "62") (name "MOT-EN") (class "Default")
      (node (ref "ARDUINO_MEGA_1") (pin "D38") (pinfunction "D38(PD7/T0)_D38") (pintype "bidirectional"))
      (node (ref "R7") (pin "1") (pinfunction "1_1") (pintype "passive"))
    )
    (net (code "63") (name "MS1") (class "Default")
      (node (ref "ARDUINO_MEGA_1") (pin "D37") (pinfunction "D37(PC0/A8)_D37") (pintype "bidirectional"))
      (node (ref "D-SUB50") (pin "23") (pinfunction "23_23") (pintype "passive"))
    )
    (net (code "64") (name "MS2") (class "Default")
      (node (ref "ARDUINO_MEGA_1") (pin "D36") (pinfunction "D36(PC1/A9)_D36") (pintype "bidirectional"))
      (node (ref "D-SUB50") (pin "7") (pinfunction "7_7") (pintype "passive"))
    )
    (net (code "65") (name "MS3") (class "Default")
      (node (ref "ARDUINO_MEGA_1") (pin "D35") (pinfunction "D35(PC2/A10)_D35") (pintype "bidirectional"))
      (node (ref "D-SUB50") (pin "24") (pinfunction "24_24") (pintype "passive"))
    )
    (net (code "66") (name "MS4") (class "Default")
      (node (ref "ARDUINO_MEGA_1") (pin "D34") (pinfunction "D34(PC3/A11)_D34") (pintype "bidirectional"))
      (node (ref "D-SUB50") (pin "8") (pinfunction "8_8") (pintype "passive"))
    )
    (net (code "67") (name "MS5") (class "Default")
      (node (ref "ARDUINO_MEGA_1") (pin "D33") (pinfunction "D33(PC4/A12)_D33") (pintype "bidirectional"))
      (node (ref "D-SUB50") (pin "6") (pinfunction "6_6") (pintype "passive"))
    )
    (net (code "68") (name "MS6") (class "Default")
      (node (ref "ARDUINO_MEGA_1") (pin "D32") (pinfunction "D32(PC5/A13)_D32") (pintype "bidirectional"))
      (node (ref "D-SUB50") (pin "22") (pinfunction "22_22") (pintype "passive"))
    )
    (net (code "69") (name "Net-(ARDUINO_MEGA_1-~{RESET})") (class "Default")
      (node (ref "ARDUINO_MEGA_1") (pin "RST") (pinfunction "~{RESET}_RST") (pintype "bidirectional"))
      (node (ref "RESET-LOGIC") (pin "1") (pinfunction "1_1") (pintype "passive"))
    )
    (net (code "70") (name "Net-(E-STOPB-KL)") (class "Default")
      (node (ref "E-STOP") (pin "2") (pinfunction "KL_2") (pintype "passive"))
      (node (ref "MOT-EN") (pin "C") (pinfunction "C_C") (pintype "passive"))
    )
    (net (code "71") (name "Net-(IC2-FILTER)") (class "Default")
      (node (ref "C3") (pin "2") (pinfunction "2_2") (pintype "passive"))
      (node (ref "IC2") (pin "6") (pinfunction "FILTER_6") (pintype "bidirectional"))
    )
    (net (code "72") (name "Net-(IC3-FILTER)") (class "Default")
      (node (ref "C4") (pin "1") (pinfunction "1_1") (pintype "passive"))
      (node (ref "IC3") (pin "6") (pinfunction "FILTER_6") (pintype "bidirectional"))
    )
    (net (code "73") (name "Net-(IC5-FILTER)") (class "Default")
      (node (ref "C6") (pin "2") (pinfunction "2_2") (pintype "passive"))
      (node (ref "IC5") (pin "6") (pinfunction "FILTER_6") (pintype "bidirectional"))
    )
    (net (code "74") (name "Net-(IC6-FILTER)") (class "Default")
      (node (ref "C7") (pin "1") (pinfunction "1_1") (pintype "passive"))
      (node (ref "IC6") (pin "6") (pinfunction "FILTER_6") (pintype "bidirectional"))
    )
    (net (code "75") (name "Net-(IC8-FILTER)") (class "Default")
      (node (ref "C8") (pin "2") (pinfunction "2_2") (pintype "passive"))
      (node (ref "IC8") (pin "6") (pinfunction "FILTER_6") (pintype "bidirectional"))
    )
    (net (code "76") (name "Net-(IC9-FILTER)") (class "Default")
      (node (ref "C9") (pin "1") (pinfunction "1_1") (pintype "passive"))
      (node (ref "IC9") (pin "6") (pinfunction "FILTER_6") (pintype "bidirectional"))
    )
    (net (code "77") (name "Net-(MOT-EN-PadB)") (class "Default")
      (node (ref "MOT-EN") (pin "B") (pinfunction "B_B") (pintype "passive"))
      (node (ref "R7") (pin "2") (pinfunction "2_2") (pintype "passive"))
    )
    (net (code "78") (name "Net-(MOT-RELA-2)") (class "Default")
      (node (ref "MOT-EN") (pin "E") (pinfunction "E_E") (pintype "passive"))
      (node (ref "MOT-REL") (pin "A2") (pinfunction "2_A2") (pintype "passive"))
    )
    (net (code "79") (name "PWM1") (class "Default")
      (node (ref "ARDUINO_MEGA_1") (pin "D5") (pinfunction "(PWM)D05(PE3/AIN1/OC3A)_D5") (pintype "bidirectional"))
      (node (ref "MOT12") (pin "6") (pinfunction "ENABLE_A_6") (pintype "input"))
    )
    (net (code "80") (name "PWM2") (class "Default")
      (node (ref "ARDUINO_MEGA_1") (pin "D2") (pinfunction "(PWM)D02(PE4/INT4/OC3B)_D2") (pintype "bidirectional"))
      (node (ref "MOT12") (pin "11") (pinfunction "ENABLE_B_11") (pintype "input"))
    )
    (net (code "81") (name "PWM3") (class "Default")
      (node (ref "ARDUINO_MEGA_1") (pin "D3") (pinfunction "(PWM)D03(PE5/INT5/OC3C)_D3") (pintype "bidirectional"))
      (node (ref "MOT34") (pin "6") (pinfunction "ENABLE_A_6") (pintype "input"))
    )
    (net (code "82") (name "PWM4") (class "Default")
      (node (ref "ARDUINO_MEGA_1") (pin "D6") (pinfunction "(PWM)D06(PH3/OC4A)_D6") (pintype "bidirectional"))
      (node (ref "MOT34") (pin "11") (pinfunction "ENABLE_B_11") (pintype "input"))
    )
    (net (code "83") (name "PWM5") (class "Default")
      (node (ref "ARDUINO_MEGA_1") (pin "D7") (pinfunction "(PWM)D07(PH4/OC4B)_D7") (pintype "bidirectional"))
      (node (ref "MOT56") (pin "6") (pinfunction "ENABLE_A_6") (pintype "input"))
    )
    (net (code "84") (name "PWM6") (class "Default")
      (node (ref "ARDUINO_MEGA_1") (pin "D8") (pinfunction "(PWM)D08(PH5/OC4C)_D8") (pintype "bidirectional"))
      (node (ref "MOT56") (pin "11") (pinfunction "ENABLE_B_11") (pintype "input"))
    )
    (net (code "85") (name "RP-ARX{slash}PTX") (class "Default")
      (node (ref "RASPBERRY-PY") (pin "8") (pinfunction "TXD_8") (pintype "bidirectional"))
      (node (ref "U1") (pin "6") (pinfunction "A5_6") (pintype "bidirectional"))
    )
    (net (code "86") (name "RP-ATX{slash}PRX") (class "Default")
      (node (ref "RASPBERRY-PY") (pin "10") (pinfunction "RXD_10") (pintype "bidirectional"))
      (node (ref "U1") (pin "7") (pinfunction "A6_7") (pintype "bidirectional"))
    )
    (net (code "87") (name "RP-MISO") (class "Default")
      (node (ref "RASPBERRY-PY") (pin "21") (pinfunction "SPI_MISO_21") (pintype "bidirectional"))
      (node (ref "U1") (pin "3") (pinfunction "A2_3") (pintype "bidirectional"))
    )
    (net (code "88") (name "RP-MOSI") (class "Default")
      (node (ref "RASPBERRY-PY") (pin "19") (pinfunction "SPI_MOSI_19") (pintype "bidirectional"))
      (node (ref "U1") (pin "1") (pinfunction "A1_1") (pintype "bidirectional"))
    )
    (net (code "89") (name "RP-SCK") (class "Default")
      (node (ref "RASPBERRY-PY") (pin "23") (pinfunction "SPI_SCLK_23") (pintype "bidirectional"))
      (node (ref "U1") (pin "4") (pinfunction "A3_4") (pintype "bidirectional"))
    )
    (net (code "90") (name "RP-SCL") (class "Default")
      (node (ref "RASPBERRY-PY") (pin "5") (pinfunction "SCL_5") (pintype "bidirectional"))
      (node (ref "U1") (pin "9") (pinfunction "A8_9") (pintype "bidirectional"))
    )
    (net (code "91") (name "RP-SDA") (class "Default")
      (node (ref "RASPBERRY-PY") (pin "3") (pinfunction "SDA_3") (pintype "bidirectional"))
      (node (ref "U1") (pin "8") (pinfunction "A7_8") (pintype "bidirectional"))
    )
    (net (code "92") (name "RP-SS") (class "Default")
      (node (ref "RASPBERRY-PY") (pin "24") (pinfunction "SPI_CE0_24") (pintype "bidirectional"))
      (node (ref "U1") (pin "5") (pinfunction "A4_5") (pintype "bidirectional"))
    )
    (net (code "93") (name "SEN_1") (class "Default")
      (node (ref "IC2") (pin "1") (pinfunction "IP+_1") (pintype "passive"))
      (node (ref "IC2") (pin "2") (pinfunction "IP+1_2") (pintype "passive"))
      (node (ref "MOT12") (pin "1") (pinfunction "SEN_A_1") (pintype "input"))
    )
    (net (code "94") (name "SEN_2") (class "Default")
      (node (ref "IC3") (pin "1") (pinfunction "IP+_1") (pintype "passive"))
      (node (ref "IC3") (pin "2") (pinfunction "IP+1_2") (pintype "passive"))
      (node (ref "MOT12") (pin "15") (pinfunction "SEN_B_15") (pintype "input"))
    )
    (net (code "95") (name "SEN_3") (class "Default")
      (node (ref "IC5") (pin "1") (pinfunction "IP+_1") (pintype "passive"))
      (node (ref "IC5") (pin "2") (pinfunction "IP+1_2") (pintype "passive"))
      (node (ref "MOT34") (pin "1") (pinfunction "SEN_A_1") (pintype "input"))
    )
    (net (code "96") (name "SEN_4") (class "Default")
      (node (ref "IC6") (pin "1") (pinfunction "IP+_1") (pintype "passive"))
      (node (ref "IC6") (pin "2") (pinfunction "IP+1_2") (pintype "passive"))
      (node (ref "MOT34") (pin "15") (pinfunction "SEN_B_15") (pintype "input"))
    )
    (net (code "97") (name "SEN_5") (class "Default")
      (node (ref "IC8") (pin "1") (pinfunction "IP+_1") (pintype "passive"))
      (node (ref "IC8") (pin "2") (pinfunction "IP+1_2") (pintype "passive"))
      (node (ref "MOT56") (pin "1") (pinfunction "SEN_A_1") (pintype "input"))
    )
    (net (code "98") (name "SEN_6") (class "Default")
      (node (ref "IC9") (pin "1") (pinfunction "IP+_1") (pintype "passive"))
      (node (ref "IC9") (pin "2") (pinfunction "IP+1_2") (pintype "passive"))
      (node (ref "MOT56") (pin "15") (pinfunction "SEN_B_15") (pintype "input"))
    )
    (net (code "99") (name "V+") (class "Default")
      (node (ref "ATX") (pin "10") (pinfunction "VCC/2_10") (pintype "power_in"))
      (node (ref "ATX") (pin "11") (pinfunction "VCC/2_11") (pintype "power_in"))
      (node (ref "E-STOP") (pin "1") (pinfunction "KL_1") (pintype "passive"))
      (node (ref "MOT-REL") (pin "14") (pinfunction "S_14") (pintype "passive"))
    )
    (net (code "100") (name "V-OFF") (class "Default")
      (node (ref "ARDUINO_MEGA_1") (pin "A1") (pinfunction "A01(PF1/ADC1)_A1") (pintype "bidirectional"))
      (node (ref "C2") (pin "1") (pinfunction "1_1") (pintype "passive"))
      (node (ref "R-OFF") (pin "2") (pinfunction "S_2") (pintype "passive"))
    )
    (net (code "101") (name "V-REF") (class "Default")
      (node (ref "ARDUINO_MEGA_1") (pin "AREF") (pinfunction "AREF_AREF") (pintype "bidirectional"))
      (node (ref "V-REF") (pin "2") (pinfunction "OUT_2") (pintype "passive"))
    )
    (net (code "102") (name "VDD") (class "Default")
      (node (ref "C1") (pin "+") (pinfunction "+_+") (pintype "passive"))
      (node (ref "D1") (pin "C") (pinfunction "C_C") (pintype "passive"))
      (node (ref "D11") (pin "C") (pinfunction "C_C") (pintype "passive"))
      (node (ref "D13") (pin "C") (pinfunction "C_C") (pintype "passive"))
      (node (ref "D15") (pin "C") (pinfunction "C_C") (pintype "passive"))
      (node (ref "D17") (pin "C") (pinfunction "C_C") (pintype "passive"))
      (node (ref "D19") (pin "C") (pinfunction "C_C") (pintype "passive"))
      (node (ref "D21") (pin "C") (pinfunction "C_C") (pintype "passive"))
      (node (ref "D23") (pin "C") (pinfunction "C_C") (pintype "passive"))
      (node (ref "D3") (pin "C") (pinfunction "C_C") (pintype "passive"))
      (node (ref "D5") (pin "C") (pinfunction "C_C") (pintype "passive"))
      (node (ref "D7") (pin "C") (pinfunction "C_C") (pintype "passive"))
      (node (ref "D9") (pin "C") (pinfunction "C_C") (pintype "passive"))
      (node (ref "FAN-PWR1") (pin "1") (pinfunction "1_1") (pintype "passive"))
      (node (ref "FAN-PWR2") (pin "1") (pinfunction "1_1") (pintype "passive"))
      (node (ref "MOT-REL") (pin "11") (pinfunction "P_11") (pintype "passive"))
      (node (ref "MOT12") (pin "4") (pinfunction "VS_4") (pintype "power_in"))
      (node (ref "MOT34") (pin "4") (pinfunction "VS_4") (pintype "power_in"))
      (node (ref "MOT56") (pin "4") (pinfunction "VS_4") (pintype "power_in"))
    )
    (net (code "103") (name "VLED1") (class "Default")
      (node (ref "D-SUB50") (pin "11") (pinfunction "11_11") (pintype "passive"))
      (node (ref "R1") (pin "2") (pinfunction "2_2") (pintype "passive"))
    )
    (net (code "104") (name "VLED2") (class "Default")
      (node (ref "D-SUB50") (pin "27") (pinfunction "27_27") (pintype "passive"))
      (node (ref "R2") (pin "2") (pinfunction "2_2") (pintype "passive"))
    )
    (net (code "105") (name "VLED3") (class "Default")
      (node (ref "D-SUB50") (pin "10") (pinfunction "10_10") (pintype "passive"))
      (node (ref "R3") (pin "2") (pinfunction "2_2") (pintype "passive"))
    )
    (net (code "106") (name "VLED4") (class "Default")
      (node (ref "D-SUB50") (pin "26") (pinfunction "26_26") (pintype "passive"))
      (node (ref "R4") (pin "2") (pinfunction "2_2") (pintype "passive"))
    )
    (net (code "107") (name "VLED5") (class "Default")
      (node (ref "D-SUB50") (pin "9") (pinfunction "9_9") (pintype "passive"))
      (node (ref "R5") (pin "2") (pinfunction "2_2") (pintype "passive"))
    )
    (net (code "108") (name "VLED6") (class "Default")
      (node (ref "D-SUB50") (pin "25") (pinfunction "25_25") (pintype "passive"))
      (node (ref "R6") (pin "2") (pinfunction "2_2") (pintype "passive"))
    )
    (net (code "109") (name "unconnected-(ARDUINO_MEGA_1-(PWM)D04(PG5{slash}OC0B)-PadD4)") (class "Default")
      (node (ref "ARDUINO_MEGA_1") (pin "D4") (pinfunction "(PWM)D04(PG5/OC0B)_D4") (pintype "bidirectional"))
    )
    (net (code "110") (name "unconnected-(ARDUINO_MEGA_1-(PWM)D09(PH6{slash}OC2B)-PadD9)") (class "Default")
      (node (ref "ARDUINO_MEGA_1") (pin "D9") (pinfunction "(PWM)D09(PH6/OC2B)_D9") (pintype "bidirectional"))
    )
    (net (code "111") (name "unconnected-(ARDUINO_MEGA_1-(PWM)D44(PL5{slash}OC5C)-PadD44)") (class "Default")
      (node (ref "ARDUINO_MEGA_1") (pin "D44") (pinfunction "(PWM)D44(PL5/OC5C)_D44") (pintype "bidirectional"))
    )
    (net (code "112") (name "unconnected-(ARDUINO_MEGA_1-(PWM)D45(PL4{slash}OC5B)-PadD45)") (class "Default")
      (node (ref "ARDUINO_MEGA_1") (pin "D45") (pinfunction "(PWM)D45(PL4/OC5B)_D45") (pintype "bidirectional"))
    )
    (net (code "113") (name "unconnected-(ARDUINO_MEGA_1-(RX)D00(PE0{slash}TXD0{slash}PCINT8)-PadD0)") (class "Default")
      (node (ref "ARDUINO_MEGA_1") (pin "D0") (pinfunction "(RX)D00(PE0/TXD0/PCINT8)_D0") (pintype "bidirectional"))
    )
    (net (code "114") (name "unconnected-(ARDUINO_MEGA_1-(RX2)D17(PH0{slash}RXD2)-PadD17)") (class "Default")
      (node (ref "ARDUINO_MEGA_1") (pin "D17") (pinfunction "(RX2)D17(PH0/RXD2)_D17") (pintype "bidirectional"))
    )
    (net (code "115") (name "unconnected-(ARDUINO_MEGA_1-(RX3)D15(PJ0{slash}PCINT9{slash}RXD3)-PadD15)") (class "Default")
      (node (ref "ARDUINO_MEGA_1") (pin "D15") (pinfunction "(RX3)D15(PJ0/PCINT9/RXD3)_D15") (pintype "bidirectional"))
    )
    (net (code "116") (name "unconnected-(ARDUINO_MEGA_1-(TX)D01(PE1{slash}RXD0{slash}PCINT3)-PadD1)") (class "Default")
      (node (ref "ARDUINO_MEGA_1") (pin "D1") (pinfunction "(TX)D01(PE1/RXD0/PCINT3)_D1") (pintype "bidirectional"))
    )
    (net (code "117") (name "unconnected-(ARDUINO_MEGA_1-(TX2)D16(PH1{slash}TXD2)-PadD16)") (class "Default")
      (node (ref "ARDUINO_MEGA_1") (pin "D16") (pinfunction "(TX2)D16(PH1/TXD2)_D16") (pintype "bidirectional"))
    )
    (net (code "118") (name "unconnected-(ARDUINO_MEGA_1-(TX3)D14(PJ1{slash}PCINT10{slash}TXD3)-PadD14)") (class "Default")
      (node (ref "ARDUINO_MEGA_1") (pin "D14") (pinfunction "(TX3)D14(PJ1/PCINT10/TXD3)_D14") (pintype "bidirectional"))
    )
    (net (code "119") (name "unconnected-(ARDUINO_MEGA_1-+VIN-PadVIN)") (class "Default")
      (node (ref "ARDUINO_MEGA_1") (pin "VIN") (pinfunction "+VIN_VIN") (pintype "bidirectional"))
    )
    (net (code "120") (name "unconnected-(ARDUINO_MEGA_1-A07(PF7{slash}ADC7{slash}TDI)-PadA7)") (class "Default")
      (node (ref "ARDUINO_MEGA_1") (pin "A7") (pinfunction "A07(PF7/ADC7/TDI)_A7") (pintype "bidirectional"))
    )
    (net (code "121") (name "unconnected-(ARDUINO_MEGA_1-D30(PC7{slash}A15)-PadD30)") (class "Default")
      (node (ref "ARDUINO_MEGA_1") (pin "D30") (pinfunction "D30(PC7/A15)_D30") (pintype "bidirectional"))
    )
    (net (code "122") (name "unconnected-(ARDUINO_MEGA_1-D31(PC6{slash}A14)-PadD31)") (class "Default")
      (node (ref "ARDUINO_MEGA_1") (pin "D31") (pinfunction "D31(PC6/A14)_D31") (pintype "bidirectional"))
    )
    (net (code "123") (name "unconnected-(ARDUINO_MEGA_1-D39(PG2{slash}ALE)-PadD39)") (class "Default")
      (node (ref "ARDUINO_MEGA_1") (pin "D39") (pinfunction "D39(PG2/ALE)_D39") (pintype "bidirectional"))
    )
    (net (code "124") (name "unconnected-(ARDUINO_MEGA_1-D40(PG1{slash}RD)-PadD40)") (class "Default")
      (node (ref "ARDUINO_MEGA_1") (pin "D40") (pinfunction "D40(PG1/RD)_D40") (pintype "bidirectional"))
    )
    (net (code "125") (name "unconnected-(ARDUINO_MEGA_1-D41(PG0{slash}WR)-PadD41)") (class "Default")
      (node (ref "ARDUINO_MEGA_1") (pin "D41") (pinfunction "D41(PG0/WR)_D41") (pintype "bidirectional"))
    )
    (net (code "126") (name "unconnected-(ARDUINO_MEGA_1-D42(PL7)-PadD42)") (class "Default")
      (node (ref "ARDUINO_MEGA_1") (pin "D42") (pinfunction "D42(PL7)_D42") (pintype "bidirectional"))
    )
    (net (code "127") (name "unconnected-(ARDUINO_MEGA_1-D43(PL6)-PadD43)") (class "Default")
      (node (ref "ARDUINO_MEGA_1") (pin "D43") (pinfunction "D43(PL6)_D43") (pintype "bidirectional"))
    )
    (net (code "128") (name "unconnected-(ARDUINO_MEGA_1-Pad+3V3)") (class "Default")
      (node (ref "ARDUINO_MEGA_1") (pin "+3V3") (pinfunction "+3V3_+3V3") (pintype "bidirectional"))
    )
    (net (code "129") (name "unconnected-(ARDUINO_MEGA_1-PadIOREF)") (class "Default")
      (node (ref "ARDUINO_MEGA_1") (pin "IOREF") (pinfunction "IOREF_IOREF") (pintype "bidirectional"))
    )
    (net (code "130") (name "unconnected-(ATXF-5V-ST_BY-Pad9)") (class "Default")
      (node (ref "ATX") (pin "9") (pinfunction "5V-ST_BY_9") (pintype "output"))
    )
    (net (code "131") (name "unconnected-(ATXF-PWR_OK-Pad7)") (class "Default")
      (node (ref "ATX") (pin "7") (pinfunction "PWR_OK_7") (pintype "passive"))
    )
    (net (code "132") (name "unconnected-(D-SUB50-Pad37)") (class "Default")
      (node (ref "D-SUB50") (pin "37") (pinfunction "37_37") (pintype "passive"))
    )
    (net (code "133") (name "unconnected-(D-SUB50-Pad38)") (class "Default")
      (node (ref "D-SUB50") (pin "38") (pinfunction "38_38") (pintype "passive"))
    )
    (net (code "134") (name "unconnected-(D-SUB50-Pad39)") (class "Default")
      (node (ref "D-SUB50") (pin "39") (pinfunction "39_39") (pintype "passive"))
    )
    (net (code "135") (name "unconnected-(D-SUB50-Pad40)") (class "Default")
      (node (ref "D-SUB50") (pin "40") (pinfunction "40_40") (pintype "passive"))
    )
    (net (code "136") (name "unconnected-(D-SUB50-Pad41)") (class "Default")
      (node (ref "D-SUB50") (pin "41") (pinfunction "41_41") (pintype "passive"))
    )
    (net (code "137") (name "unconnected-(D-SUB50-Pad42)") (class "Default")
      (node (ref "D-SUB50") (pin "42") (pinfunction "42_42") (pintype "passive"))
    )
    (net (code "138") (name "unconnected-(D-SUB50-Pad43)") (class "Default")
      (node (ref "D-SUB50") (pin "43") (pinfunction "43_43") (pintype "passive"))
    )
    (net (code "139") (name "unconnected-(D-SUB50-Pad44)") (class "Default")
      (node (ref "D-SUB50") (pin "44") (pinfunction "44_44") (pintype "passive"))
    )
    (net (code "140") (name "unconnected-(D-SUB50-PadG1)") (class "Default")
      (node (ref "D-SUB50") (pin "G1") (pinfunction "G1_G1") (pintype "passive"))
    )
    (net (code "141") (name "unconnected-(D-SUB50-PadG2)") (class "Default")
      (node (ref "D-SUB50") (pin "G2") (pinfunction "G2_G2") (pintype "passive"))
    )
    (net (code "142") (name "unconnected-(RASPBERRY-PY-GPIO04-Pad7)") (class "Default")
      (node (ref "RASPBERRY-PY") (pin "7") (pinfunction "GPIO04_7") (pintype "bidirectional"))
    )
    (net (code "143") (name "unconnected-(RASPBERRY-PY-GPIO05-Pad29)") (class "Default")
      (node (ref "RASPBERRY-PY") (pin "29") (pinfunction "GPIO05_29") (pintype "no_connect"))
    )
    (net (code "144") (name "unconnected-(RASPBERRY-PY-GPIO06-Pad31)") (class "Default")
      (node (ref "RASPBERRY-PY") (pin "31") (pinfunction "GPIO06_31") (pintype "no_connect"))
    )
    (net (code "145") (name "unconnected-(RASPBERRY-PY-GPIO12-Pad32)") (class "Default")
      (node (ref "RASPBERRY-PY") (pin "32") (pinfunction "GPIO12_32") (pintype "no_connect"))
    )
    (net (code "146") (name "unconnected-(RASPBERRY-PY-GPIO13-Pad33)") (class "Default")
      (node (ref "RASPBERRY-PY") (pin "33") (pinfunction "GPIO13_33") (pintype "no_connect"))
    )
    (net (code "147") (name "unconnected-(RASPBERRY-PY-GPIO16-Pad36)") (class "Default")
      (node (ref "RASPBERRY-PY") (pin "36") (pinfunction "GPIO16_36") (pintype "no_connect"))
    )
    (net (code "148") (name "unconnected-(RASPBERRY-PY-GPIO18-Pad12)") (class "Default")
      (node (ref "RASPBERRY-PY") (pin "12") (pinfunction "GPIO18_12") (pintype "bidirectional"))
    )
    (net (code "149") (name "unconnected-(RASPBERRY-PY-GPIO19-Pad35)") (class "Default")
      (node (ref "RASPBERRY-PY") (pin "35") (pinfunction "GPIO19_35") (pintype "no_connect"))
    )
    (net (code "150") (name "unconnected-(RASPBERRY-PY-GPIO20-Pad38)") (class "Default")
      (node (ref "RASPBERRY-PY") (pin "38") (pinfunction "GPIO20_38") (pintype "no_connect"))
    )
    (net (code "151") (name "unconnected-(RASPBERRY-PY-GPIO21-Pad40)") (class "Default")
      (node (ref "RASPBERRY-PY") (pin "40") (pinfunction "GPIO21_40") (pintype "no_connect"))
    )
    (net (code "152") (name "unconnected-(RASPBERRY-PY-GPIO22-Pad15)") (class "Default")
      (node (ref "RASPBERRY-PY") (pin "15") (pinfunction "GPIO22_15") (pintype "bidirectional"))
    )
    (net (code "153") (name "unconnected-(RASPBERRY-PY-GPIO23-Pad16)") (class "Default")
      (node (ref "RASPBERRY-PY") (pin "16") (pinfunction "GPIO23_16") (pintype "bidirectional"))
    )
    (net (code "154") (name "unconnected-(RASPBERRY-PY-GPIO24-Pad18)") (class "Default")
      (node (ref "RASPBERRY-PY") (pin "18") (pinfunction "GPIO24_18") (pintype "bidirectional"))
    )
    (net (code "155") (name "unconnected-(RASPBERRY-PY-GPIO25-Pad22)") (class "Default")
      (node (ref "RASPBERRY-PY") (pin "22") (pinfunction "GPIO25_22") (pintype "bidirectional"))
    )
    (net (code "156") (name "unconnected-(RASPBERRY-PY-GPIO26-Pad37)") (class "Default")
      (node (ref "RASPBERRY-PY") (pin "37") (pinfunction "GPIO26_37") (pintype "no_connect"))
    )
    (net (code "157") (name "unconnected-(RASPBERRY-PY-GPIO27-Pad13)") (class "Default")
      (node (ref "RASPBERRY-PY") (pin "13") (pinfunction "GPIO27_13") (pintype "bidirectional"))
    )
    (net (code "158") (name "unconnected-(RASPBERRY-PY-ID_SC-Pad28)") (class "Default")
      (node (ref "RASPBERRY-PY") (pin "28") (pinfunction "ID_SC_28") (pintype "no_connect"))
    )
    (net (code "159") (name "unconnected-(RASPBERRY-PY-ID_SD-Pad27)") (class "Default")
      (node (ref "RASPBERRY-PY") (pin "27") (pinfunction "ID_SD_27") (pintype "no_connect"))
    )
    (net (code "160") (name "unconnected-(RASPBERRY-PY-N.C.0-Pad4)") (class "Default")
      (node (ref "RASPBERRY-PY") (pin "4") (pinfunction "N.C.0_4") (pintype "no_connect"))
    )
    (net (code "161") (name "unconnected-(RASPBERRY-PY-N.C.1-Pad9)") (class "Default")
      (node (ref "RASPBERRY-PY") (pin "9") (pinfunction "N.C.1_9") (pintype "no_connect"))
    )
    (net (code "162") (name "unconnected-(RASPBERRY-PY-N.C.2-Pad14)") (class "Default")
      (node (ref "RASPBERRY-PY") (pin "14") (pinfunction "N.C.2_14") (pintype "no_connect"))
    )
    (net (code "163") (name "unconnected-(RASPBERRY-PY-N.C.3-Pad17)") (class "Default")
      (node (ref "RASPBERRY-PY") (pin "17") (pinfunction "N.C.3_17") (pintype "no_connect"))
    )
    (net (code "164") (name "unconnected-(RASPBERRY-PY-N.C.4-Pad20)") (class "Default")
      (node (ref "RASPBERRY-PY") (pin "20") (pinfunction "N.C.4_20") (pintype "no_connect"))
    )
    (net (code "165") (name "unconnected-(RASPBERRY-PY-N.C.5-Pad25)") (class "Default")
      (node (ref "RASPBERRY-PY") (pin "25") (pinfunction "N.C.5_25") (pintype "no_connect"))
    )
    (net (code "166") (name "unconnected-(RASPBERRY-PY-N.C.6-Pad30)") (class "Default")
      (node (ref "RASPBERRY-PY") (pin "30") (pinfunction "N.C.6_30") (pintype "no_connect"))
    )
    (net (code "167") (name "unconnected-(RASPBERRY-PY-N.C.7-Pad34)") (class "Default")
      (node (ref "RASPBERRY-PY") (pin "34") (pinfunction "N.C.7_34") (pintype "no_connect"))
    )
    (net (code "168") (name "unconnected-(RASPBERRY-PY-N.C.8-Pad39)") (class "Default")
      (node (ref "RASPBERRY-PY") (pin "39") (pinfunction "N.C.8_39") (pintype "no_connect"))
    )
    (net (code "169") (name "unconnected-(RASPBERRY-PY-SPI_CE1-Pad26)") (class "Default")
      (node (ref "RASPBERRY-PY") (pin "26") (pinfunction "SPI_CE1_26") (pintype "bidirectional"))
    )
  )
)
